# Dual_Power_Supply.net
KiCad netlist of a schematic drawn in EAGLE
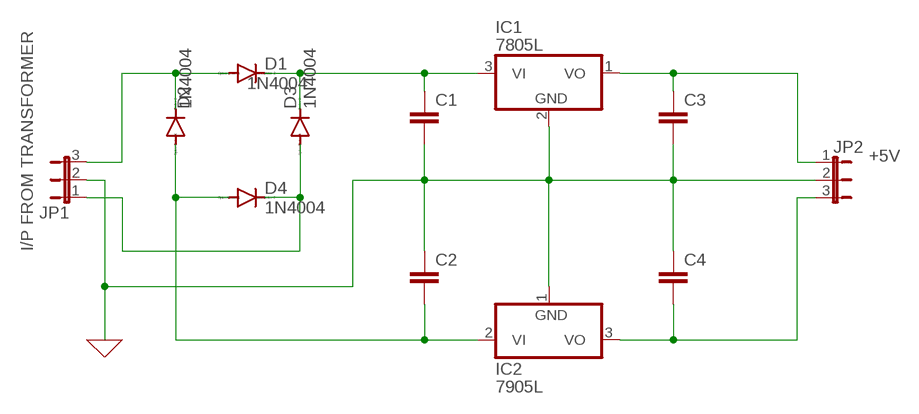
[diagram p0: schematic, sheet 1]

(export (version "E")
  (design (tool "Eeschema 10.0.6"))
  (components
    (comp (ref "C1")
      (value "C2,5-3")
      (footprint "eagle-import:C2.5-3")
      (libsource (lib "eagle-import") (part "C2,5-3"))
    )
    (comp (ref "C2")
      (value "C2,5-3")
      (footprint "eagle-import:C2.5-3")
      (libsource (lib "eagle-import") (part "C2,5-3"))
    )
    (comp (ref "C3")
      (value "C2,5-3")
      (footprint "eagle-import:C2.5-3")
      (libsource (lib "eagle-import") (part "C2,5-3"))
    )
    (comp (ref "C4")
      (value "C2,5-3")
      (footprint "eagle-import:C2.5-3")
      (libsource (lib "eagle-import") (part "C2,5-3"))
    )
    (comp (ref "D1")
      (value "1N4004")
      (footprint "eagle-import:DO41-10")
      (libsource (lib "eagle-import") (part "1N4004"))
    )
    (comp (ref "D2")
      (value "1N4004")
      (footprint "eagle-import:DO41-10")
      (libsource (lib "eagle-import") (part "1N4004"))
    )
    (comp (ref "D3")
      (value "1N4004")
      (footprint "eagle-import:DO41-10")
      (libsource (lib "eagle-import") (part "1N4004"))
    )
    (comp (ref "D4")
      (value "1N4004")
      (footprint "eagle-import:DO41-10")
      (libsource (lib "eagle-import") (part "1N4004"))
    )
    (comp (ref "IC1")
      (value "7805L")
      (footprint "eagle-import:TO92")
      (libsource (lib "eagle-import") (part "78L05"))
    )
    (comp (ref "IC3")
      (value "7905L")
      (footprint "eagle-import:TO92")
      (libsource (lib "eagle-import") (part "79L05"))
    )
    (comp (ref "JP1")
      (value "JP2E")
      (footprint "eagle-import:JP2")
      (libsource (lib "eagle-import") (part "JP2E"))
    )
    (comp (ref "JP2")
      (value "JP2E")
      (footprint "eagle-import:JP2")
      (libsource (lib "eagle-import") (part "JP2E"))
    )
  )
  (nets
    (net (code "1") (name "GND") (class "Default")
      (node (ref "C1") (pin "2") (pinfunction "2_2") (pintype "passive"))
      (node (ref "C2") (pin "1") (pinfunction "1_1") (pintype "passive"))
      (node (ref "C3") (pin "2") (pinfunction "2_2") (pintype "passive"))
      (node (ref "C4") (pin "1") (pinfunction "1_1") (pintype "passive"))
      (node (ref "IC1") (pin "2") (pinfunction "GND_2") (pintype "passive"))
      (node (ref "IC3") (pin "1") (pinfunction "GND_1") (pintype "passive"))
      (node (ref "JP1") (pin "2") (pinfunction "2_2") (pintype "passive"))
      (node (ref "JP2") (pin "2") (pinfunction "2_2") (pintype "passive"))
    )
    (net (code "2") (name "Net-(D1-PadA)") (class "Default")
      (node (ref "D1") (pin "A") (pinfunction "A_A") (pintype "passive"))
      (node (ref "D2") (pin "C") (pinfunction "C_C") (pintype "passive"))
      (node (ref "JP1") (pin "3") (pinfunction "3_3") (pintype "passive"))
    )
    (net (code "3") (name "Net-(D3-PadA)") (class "Default")
      (node (ref "D3") (pin "A") (pinfunction "A_A") (pintype "passive"))
      (node (ref "D4") (pin "C") (pinfunction "C_C") (pintype "passive"))
      (node (ref "JP1") (pin "1") (pinfunction "1_1") (pintype "passive"))
    )
    (net (code "4") (name "Net-(IC1-VI)") (class "Default")
      (node (ref "C1") (pin "1") (pinfunction "1_1") (pintype "passive"))
      (node (ref "D1") (pin "C") (pinfunction "C_C") (pintype "passive"))
      (node (ref "D3") (pin "C") (pinfunction "C_C") (pintype "passive"))
      (node (ref "IC1") (pin "3") (pinfunction "VI_3") (pintype "input"))
    )
    (net (code "5") (name "Net-(IC1-VO)") (class "Default")
      (node (ref "C3") (pin "1") (pinfunction "1_1") (pintype "passive"))
      (node (ref "IC1") (pin "1") (pinfunction "VO_1") (pintype "passive"))
      (node (ref "JP2") (pin "1") (pinfunction "1_1") (pintype "passive"))
    )
    (net (code "6") (name "Net-(IC3-VI)") (class "Default")
      (node (ref "C2") (pin "2") (pinfunction "2_2") (pintype "passive"))
      (node (ref "D2") (pin "A") (pinfunction "A_A") (pintype "passive"))
      (node (ref "D4") (pin "A") (pinfunction "A_A") (pintype "passive"))
      (node (ref "IC3") (pin "2") (pinfunction "VI_2") (pintype "input"))
    )
    (net (code "7") (name "Net-(IC3-VO)") (class "Default")
      (node (ref "C4") (pin "2") (pinfunction "2_2") (pintype "passive"))
      (node (ref "IC3") (pin "3") (pinfunction "VO_3") (pintype "passive"))
      (node (ref "JP2") (pin "3") (pinfunction "3_3") (pintype "passive"))
    )
  )
)
